# DataLogger_XIAO.net
KiCad netlist of a schematic drawn in Altium Designer
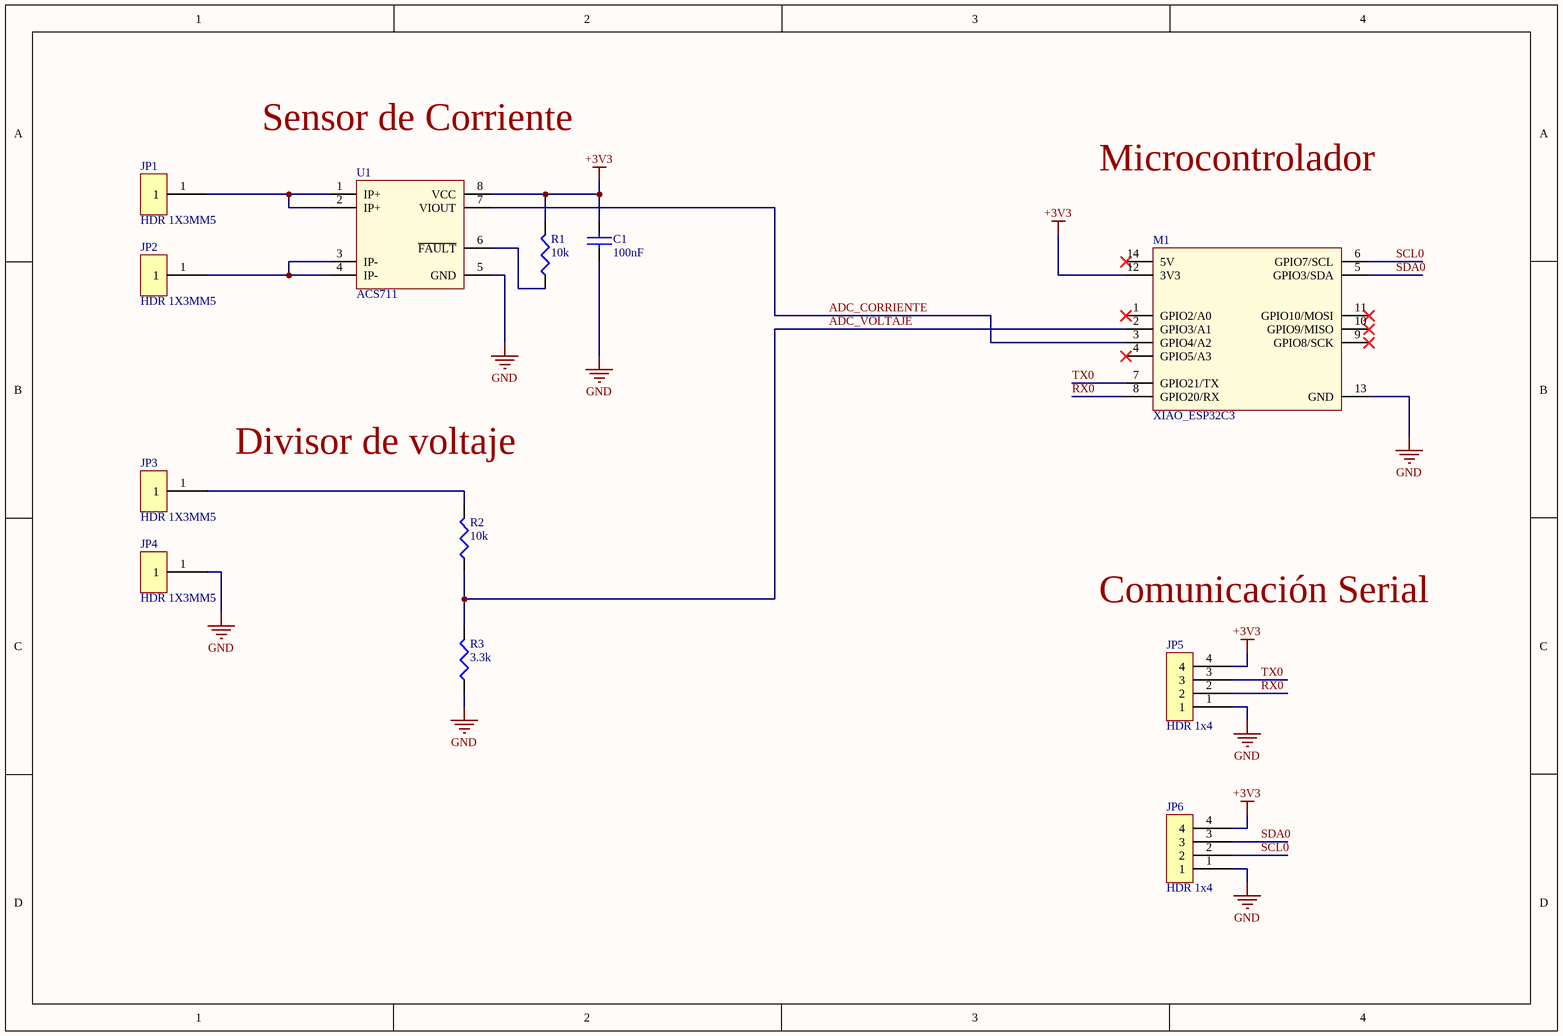
[diagram p0: DataLogger_XIAO.SchDoc]

(export (version "E")
  (design (tool "Eeschema 10.0.6"))
  (components
    (comp (ref "C1")
      (value "100nF")
      (footprint "c0603")
      (description "Multilayer Ceramic Capacitor, 0.1 uF, 50 V, ï¿½ 10%, X7R, 0603 [1608 Metric]")
      (fields
        (field (name "MANUFACTURER") "Kyocera AVX")
        (field (name "MANUFACTURER PART NUMBER") "06035C104K4Z4A")
      )
      (libsource (lib "DronLoRa") (part "06035C104K4Z4A"))
    )
    (comp (ref "JP1")
      (value "HDR 1X3MM5")
      (footprint "TERMINAL 1X3.55")
      (description "BERGSTIK 3.5 MM")
      (fields
        (field (name "MANUFACTURER") "FCI")
        (field (name "MANUFACTURER PART NUMBER") "68000-103HLF")
        (field (name ".CREATOR") "MM")
      )
      (libsource (lib "DronLoRa") (part "PIN3MM5"))
    )
    (comp (ref "JP2")
      (value "HDR 1X3MM5")
      (footprint "TERMINAL 1X3.55")
      (description "BERGSTIK 3.5 MM")
      (fields
        (field (name "MANUFACTURER") "FCI")
        (field (name "MANUFACTURER PART NUMBER") "68000-103HLF")
        (field (name ".CREATOR") "MM")
      )
      (libsource (lib "DronLoRa") (part "PIN3MM5"))
    )
    (comp (ref "JP3")
      (value "HDR 1X3MM5")
      (footprint "TERMINAL 1X3.55")
      (description "BERGSTIK 3.5 MM")
      (fields
        (field (name "MANUFACTURER") "FCI")
        (field (name "MANUFACTURER PART NUMBER") "68000-103HLF")
        (field (name ".CREATOR") "MM")
      )
      (libsource (lib "DronLoRa") (part "PIN3MM5"))
    )
    (comp (ref "JP4")
      (value "HDR 1X3MM5")
      (footprint "TERMINAL 1X3.55")
      (description "BERGSTIK 3.5 MM")
      (fields
        (field (name "MANUFACTURER") "FCI")
        (field (name "MANUFACTURER PART NUMBER") "68000-103HLF")
        (field (name ".CREATOR") "MM")
      )
      (libsource (lib "DronLoRa") (part "PIN3MM5"))
    )
    (comp (ref "JP5")
      (value "HDR 1x4")
      (footprint "Hdr_1x4_2.54MM")
      (description "Conn Unshrouded Header HDR 4 POS 2.54mm Solder ST Top Entry Thru-Hole BergStik® Bulk")
      (fields
        (field (name "MANUFACTURER") "Amphenol ICC")
        (field (name "MANUFACTURER PART NUMBER") "68000-104HLF")
      )
      (libsource (lib "DronLoRa") (part "68000-104HLF"))
    )
    (comp (ref "JP6")
      (value "HDR 1x4")
      (footprint "Hdr_1x4_2.54MM")
      (description "Conn Unshrouded Header HDR 4 POS 2.54mm Solder ST Top Entry Thru-Hole BergStik® Bulk")
      (fields
        (field (name "MANUFACTURER") "Amphenol ICC")
        (field (name "MANUFACTURER PART NUMBER") "68000-104HLF")
      )
      (libsource (lib "DronLoRa") (part "68000-104HLF"))
    )
    (comp (ref "M1")
      (value "XIAO_ESP32C3")
      (footprint "MODULE_XIAO_ESP32C3")
      (description "Seeed Studio Xiao ESP32C3 Wifi+b")
      (fields
        (field (name "MANUFACTURER") "Seeed Studio")
        (field (name "MANUFACTURER PART NUMBER") "113991054")
      )
      (libsource (lib "DronLoRa") (part "113991054"))
    )
    (comp (ref "R1")
      (value "10k")
      (footprint "R0603")
      (description "RES SMD 10K OHM 1% 1/8W 0603")
      (fields
        (field (name "MANUFACTURER") "Yageo")
        (field (name "MANUFACTURER PART NUMBER") "RC0805FR-0710KL")
        (field (name ".CREATOR") "MM")
        (field (name ".CHECKED PCB") "RF")
        (field (name ".CHECKED SCH") "RF")
      )
      (libsource (lib "DronLoRa") (part "TP0603T10K0P0510Z"))
    )
    (comp (ref "R2")
      (value "10k")
      (footprint "R0603")
      (description "RES SMD 10K OHM 1% 1/8W 0603")
      (fields
        (field (name "MANUFACTURER") "Yageo")
        (field (name "MANUFACTURER PART NUMBER") "RC0805FR-0710KL")
        (field (name ".CREATOR") "MM")
        (field (name ".CHECKED PCB") "RF")
        (field (name ".CHECKED SCH") "RF")
      )
      (libsource (lib "DronLoRa") (part "TP0603T10K0P0510Z"))
    )
    (comp (ref "R3")
      (value "3.3k")
      (footprint "R0603")
      (description "RES SMD 10K OHM 1% 1/8W 0603")
      (fields
        (field (name "MANUFACTURER") "Yageo")
        (field (name "MANUFACTURER PART NUMBER") "RC0805FR-0710KL")
        (field (name ".CREATOR") "MM")
        (field (name ".CHECKED PCB") "RF")
        (field (name ".CHECKED SCH") "RF")
      )
      (libsource (lib "DronLoRa") (part "TP0603T10K0P0510Z"))
    )
    (comp (ref "U1")
      (value "ACS711")
      (footprint "SOIC-8N-ACS711")
      (description "SENSOR CURRENT HALL 25A AC/DC")
      (fields
        (field (name "MANUFACTURER") "Allegro MicroSystems")
        (field (name "MANUFACTURER PART NUMBER") "ACS711ELCTR-25AB-T")
      )
      (libsource (lib "DronLoRa") (part "ACS711ELCTR-25AB-T"))
    )
  )
  (nets
    (net (code "1") (name "+3V3") (class "Default")
      (node (ref "C1") (pin "1") (pinfunction "1_1") (pintype "passive"))
      (node (ref "JP5") (pin "4") (pinfunction "4_4") (pintype "passive"))
      (node (ref "JP6") (pin "4") (pinfunction "4_4") (pintype "passive"))
      (node (ref "M1") (pin "12") (pinfunction "3V3_12") (pintype "passive"))
      (node (ref "R1") (pin "2") (pinfunction "2_2") (pintype "passive"))
      (node (ref "U1") (pin "8") (pinfunction "VCC_8") (pintype "passive"))
    )
    (net (code "2") (name "/ADC_CORRIENTE") (class "Default")
      (node (ref "M1") (pin "3") (pinfunction "GPIO4/A2_3") (pintype "passive"))
      (node (ref "U1") (pin "7") (pinfunction "VIOUT_7") (pintype "passive"))
    )
    (net (code "3") (name "/ADC_VOLTAJE") (class "Default")
      (node (ref "M1") (pin "2") (pinfunction "GPIO3/A1_2") (pintype "passive"))
      (node (ref "R2") (pin "1") (pinfunction "1_1") (pintype "passive"))
      (node (ref "R3") (pin "2") (pinfunction "2_2") (pintype "passive"))
    )
    (net (code "4") (name "/RX0") (class "Default")
      (node (ref "JP5") (pin "2") (pinfunction "2_2") (pintype "passive"))
      (node (ref "M1") (pin "8") (pinfunction "GPIO20/RX_8") (pintype "passive"))
    )
    (net (code "5") (name "/SCL0") (class "Default")
      (node (ref "JP6") (pin "2") (pinfunction "2_2") (pintype "passive"))
      (node (ref "M1") (pin "6") (pinfunction "_GPIO7/SCL_6") (pintype "passive"))
    )
    (net (code "6") (name "/SDA0") (class "Default")
      (node (ref "JP6") (pin "3") (pinfunction "3_3") (pintype "passive"))
      (node (ref "M1") (pin "5") (pinfunction "GPIO3/SDA_5") (pintype "passive"))
    )
    (net (code "7") (name "/TX0") (class "Default")
      (node (ref "JP5") (pin "3") (pinfunction "3_3") (pintype "passive"))
      (node (ref "M1") (pin "7") (pinfunction "GPIO21/TX_7") (pintype "passive"))
    )
    (net (code "8") (name "GND") (class "Default")
      (node (ref "C1") (pin "2") (pinfunction "2_2") (pintype "passive"))
      (node (ref "JP4") (pin "1") (pinfunction "1_1") (pintype "passive"))
      (node (ref "JP5") (pin "1") (pinfunction "1_1") (pintype "passive"))
      (node (ref "JP6") (pin "1") (pinfunction "1_1") (pintype "passive"))
      (node (ref "M1") (pin "13") (pinfunction "GND_13") (pintype "passive"))
      (node (ref "R3") (pin "1") (pinfunction "1_1") (pintype "passive"))
      (node (ref "U1") (pin "5") (pinfunction "GND_5") (pintype "passive"))
    )
    (net (code "9") (name "Net-(JP1-Pad1)") (class "Default")
      (node (ref "JP1") (pin "1") (pinfunction "1_1") (pintype "passive"))
      (node (ref "U1") (pin "1") (pinfunction "IP+_1") (pintype "passive"))
      (node (ref "U1") (pin "2") (pinfunction "IP+_2") (pintype "passive"))
    )
    (net (code "10") (name "Net-(JP2-Pad1)") (class "Default")
      (node (ref "JP2") (pin "1") (pinfunction "1_1") (pintype "passive"))
      (node (ref "U1") (pin "3") (pinfunction "IP-_3") (pintype "passive"))
      (node (ref "U1") (pin "4") (pinfunction "IP-_4") (pintype "passive"))
    )
    (net (code "11") (name "Net-(JP3-Pad1)") (class "Default")
      (node (ref "JP3") (pin "1") (pinfunction "1_1") (pintype "passive"))
      (node (ref "R2") (pin "2") (pinfunction "2_2") (pintype "passive"))
    )
    (net (code "12") (name "Net-(U1-~{FAULT})") (class "Default")
      (node (ref "R1") (pin "1") (pinfunction "1_1") (pintype "passive"))
      (node (ref "U1") (pin "6") (pinfunction "~{FAULT}_6") (pintype "passive"))
    )
    (net (code "13") (name "unconnected-(M1-5V-Pad14)") (class "Default")
      (node (ref "M1") (pin "14") (pinfunction "5V_14") (pintype "passive+no_connect"))
    )
    (net (code "14") (name "unconnected-(M1-GPIO2{slash}A0-Pad1)") (class "Default")
      (node (ref "M1") (pin "1") (pinfunction "GPIO2/A0_1") (pintype "passive+no_connect"))
    )
    (net (code "15") (name "unconnected-(M1-GPIO5{slash}A3-Pad4)") (class "Default")
      (node (ref "M1") (pin "4") (pinfunction "GPIO5/A3_4") (pintype "passive+no_connect"))
    )
    (net (code "16") (name "unconnected-(M1-GPIO8{slash}SCK-Pad9)") (class "Default")
      (node (ref "M1") (pin "9") (pinfunction "GPIO8/SCK_9") (pintype "passive+no_connect"))
    )
    (net (code "17") (name "unconnected-(M1-GPIO9{slash}MISO-Pad10)") (class "Default")
      (node (ref "M1") (pin "10") (pinfunction "GPIO9/MISO_10") (pintype "passive+no_connect"))
    )
    (net (code "18") (name "unconnected-(M1-GPIO10{slash}MOSI-Pad11)") (class "Default")
      (node (ref "M1") (pin "11") (pinfunction "GPIO10/MOSI_11") (pintype "passive+no_connect"))
    )
  )
)
